# WTV020.net
KiCad netlist of a schematic drawn in EAGLE
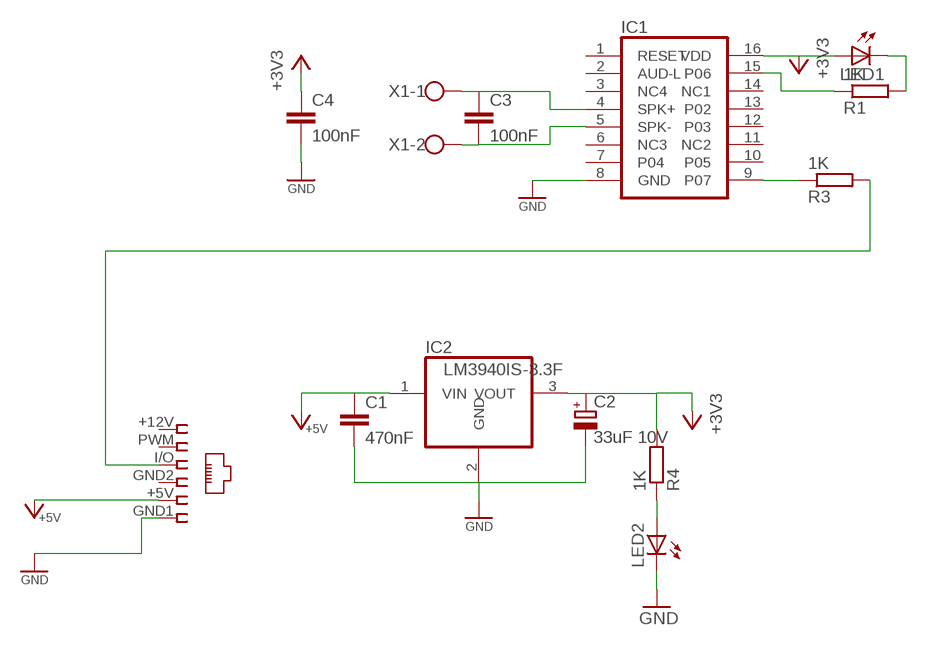
[diagram p0: schematic, sheet 1]

(export (version "E")
  (design (tool "Eeschema 10.0.6"))
  (components
    (comp (ref "C1")
      (value "470nF")
      (footprint "eagle-import:C1206")
      (libsource (lib "eagle-import") (part "C-EUC1206"))
    )
    (comp (ref "C2")
      (value "33uF 10V")
      (footprint "eagle-import:E3,5-8")
      (libsource (lib "eagle-import") (part "CPOL-EUE3.5-8"))
    )
    (comp (ref "C3")
      (value "100nF")
      (footprint "eagle-import:C1206")
      (libsource (lib "eagle-import") (part "C-EUC1206"))
    )
    (comp (ref "C4")
      (value "100nF")
      (footprint "eagle-import:C1206")
      (libsource (lib "eagle-import") (part "C-EUC1206"))
    )
    (comp (ref "I2C_IN")
      (value "I2C 1")
      (footprint "eagle-import:RJ12-STRAIGHT")
      (libsource (lib "eagle-import") (part "RJ12STRAIGHT"))
    )
    (comp (ref "IC1")
      (value "WTV020")
      (footprint "eagle-import:DIL16-6")
      (libsource (lib "eagle-import") (part "WTV020"))
    )
    (comp (ref "IC2")
      (value "LM3940IS-3.3F")
      (footprint "eagle-import:DD-3")
      (fields (field (name "MF") "TEXAS INSTRUMENTS") (field (name "MPN") "REG1117FAKTTT"))
      (libsource (lib "eagle-import") (part "LM3940IS-3.3F"))
    )
    (comp (ref "LED1")
      (value "LED3MM")
      (footprint "eagle-import:LED3MM")
      (libsource (lib "eagle-import") (part "LED3MM"))
    )
    (comp (ref "LED2")
      (value "LED3MM")
      (footprint "eagle-import:LED3MM")
      (libsource (lib "eagle-import") (part "LED3MM"))
    )
    (comp (ref "R1")
      (value "1K")
      (footprint "eagle-import:M1206")
      (libsource (lib "eagle-import") (part "R-EU_M1206"))
    )
    (comp (ref "R3")
      (value "1K")
      (footprint "eagle-import:M1206")
      (libsource (lib "eagle-import") (part "R-EU_M1206"))
    )
    (comp (ref "R4")
      (value "1K")
      (footprint "eagle-import:M1206")
      (libsource (lib "eagle-import") (part "R-EU_M1206"))
    )
    (comp (ref "X1")
      (value "W237-102")
      (footprint "eagle-import:W237-102")
      (libsource (lib "eagle-import") (part "W237-102"))
    )
  )
  (nets
    (net (code "1") (name "+3V3") (class "Default")
      (node (ref "C2") (pin "+") (pinfunction "+_+") (pintype "passive"))
      (node (ref "C4") (pin "1") (pinfunction "1_1") (pintype "passive"))
      (node (ref "IC1") (pin "16") (pinfunction "VDD_16") (pintype "power_in"))
      (node (ref "IC2") (pin "3") (pinfunction "VOUT_3") (pintype "output"))
      (node (ref "LED1") (pin "A") (pinfunction "A_A") (pintype "passive"))
      (node (ref "R4") (pin "2") (pinfunction "2_2") (pintype "passive"))
    )
    (net (code "2") (name "+5V") (class "Default")
      (node (ref "C1") (pin "1") (pinfunction "1_1") (pintype "passive"))
      (node (ref "I2C_IN") (pin "+5V") (pinfunction "5_+5V") (pintype "power_in"))
      (node (ref "IC2") (pin "1") (pinfunction "VIN_1") (pintype "input"))
    )
    (net (code "3") (name "/1") (class "Default")
      (node (ref "I2C_IN") (pin "+12V") (pinfunction "1_+12V") (pintype "power_in"))
    )
    (net (code "4") (name "/4") (class "Default")
      (node (ref "I2C_IN") (pin "GND2") (pinfunction "4_GND2") (pintype "power_in"))
    )
    (net (code "5") (name "GND") (class "Default")
      (node (ref "C1") (pin "2") (pinfunction "2_2") (pintype "passive"))
      (node (ref "C2") (pin "-") (pinfunction "-_-") (pintype "passive"))
      (node (ref "C4") (pin "2") (pinfunction "2_2") (pintype "passive"))
      (node (ref "I2C_IN") (pin "GND1") (pinfunction "6_GND1") (pintype "power_in"))
      (node (ref "IC1") (pin "8") (pinfunction "GND_8") (pintype "input"))
      (node (ref "IC2") (pin "2") (pinfunction "GND_2") (pintype "power_in"))
      (node (ref "LED2") (pin "K") (pinfunction "C_K") (pintype "passive"))
    )
    (net (code "6") (name "Net-(I2C_IN-3)") (class "Default")
      (node (ref "I2C_IN") (pin "I/O") (pinfunction "3_I/O") (pintype "bidirectional"))
      (node (ref "R3") (pin "2") (pinfunction "2_2") (pintype "passive"))
    )
    (net (code "7") (name "Net-(IC1-P06)") (class "Default")
      (node (ref "IC1") (pin "15") (pinfunction "P06_15") (pintype "output"))
      (node (ref "R1") (pin "1") (pinfunction "1_1") (pintype "passive"))
    )
    (net (code "8") (name "Net-(IC1-P07)") (class "Default")
      (node (ref "IC1") (pin "9") (pinfunction "P07_9") (pintype "input"))
      (node (ref "R3") (pin "1") (pinfunction "1_1") (pintype "passive"))
    )
    (net (code "9") (name "Net-(IC1-SPK+)") (class "Default")
      (node (ref "C3") (pin "1") (pinfunction "1_1") (pintype "passive"))
      (node (ref "IC1") (pin "4") (pinfunction "SPK+_4") (pintype "output"))
      (node (ref "X1") (pin "1") (pinfunction "KL_1") (pintype "passive"))
    )
    (net (code "10") (name "Net-(IC1-SPK-)") (class "Default")
      (node (ref "C3") (pin "2") (pinfunction "2_2") (pintype "passive"))
      (node (ref "IC1") (pin "5") (pinfunction "SPK-_5") (pintype "output"))
      (node (ref "X1") (pin "2") (pinfunction "KL_2") (pintype "passive"))
    )
    (net (code "11") (name "Net-(LED1-C)") (class "Default")
      (node (ref "LED1") (pin "K") (pinfunction "C_K") (pintype "passive"))
      (node (ref "R1") (pin "2") (pinfunction "2_2") (pintype "passive"))
    )
    (net (code "12") (name "Net-(LED2-PadA)") (class "Default")
      (node (ref "LED2") (pin "A") (pinfunction "A_A") (pintype "passive"))
      (node (ref "R4") (pin "1") (pinfunction "1_1") (pintype "passive"))
    )
    (net (code "13") (name "unconnected-(I2C_IN-2-PadPWM)") (class "Default")
      (node (ref "I2C_IN") (pin "PWM") (pinfunction "2_PWM") (pintype "bidirectional"))
    )
    (net (code "14") (name "unconnected-(IC1-AUD-L-Pad2)") (class "Default")
      (node (ref "IC1") (pin "2") (pinfunction "AUD-L_2") (pintype "output"))
    )
    (net (code "15") (name "unconnected-(IC1-NC1-Pad14)") (class "Default")
      (node (ref "IC1") (pin "14") (pinfunction "NC1_14") (pintype "no_connect"))
    )
    (net (code "16") (name "unconnected-(IC1-NC2-Pad11)") (class "Default")
      (node (ref "IC1") (pin "11") (pinfunction "NC2_11") (pintype "no_connect"))
    )
    (net (code "17") (name "unconnected-(IC1-NC3-Pad6)") (class "Default")
      (node (ref "IC1") (pin "6") (pinfunction "NC3_6") (pintype "no_connect"))
    )
    (net (code "18") (name "unconnected-(IC1-NC4-Pad3)") (class "Default")
      (node (ref "IC1") (pin "3") (pinfunction "NC4_3") (pintype "no_connect"))
    )
    (net (code "19") (name "unconnected-(IC1-P02-Pad13)") (class "Default")
      (node (ref "IC1") (pin "13") (pinfunction "P02_13") (pintype "input"))
    )
    (net (code "20") (name "unconnected-(IC1-P03-Pad12)") (class "Default")
      (node (ref "IC1") (pin "12") (pinfunction "P03_12") (pintype "input"))
    )
    (net (code "21") (name "unconnected-(IC1-P04-Pad7)") (class "Default")
      (node (ref "IC1") (pin "7") (pinfunction "P04_7") (pintype "input"))
    )
    (net (code "22") (name "unconnected-(IC1-P05-Pad10)") (class "Default")
      (node (ref "IC1") (pin "10") (pinfunction "P05_10") (pintype "input"))
    )
    (net (code "23") (name "unconnected-(IC1-RESET-Pad1)") (class "Default")
      (node (ref "IC1") (pin "1") (pinfunction "RESET_1") (pintype "input"))
    )
  )
)
